# 012_2N3906.net
KiCad netlist of a schematic drawn in Altium Designer
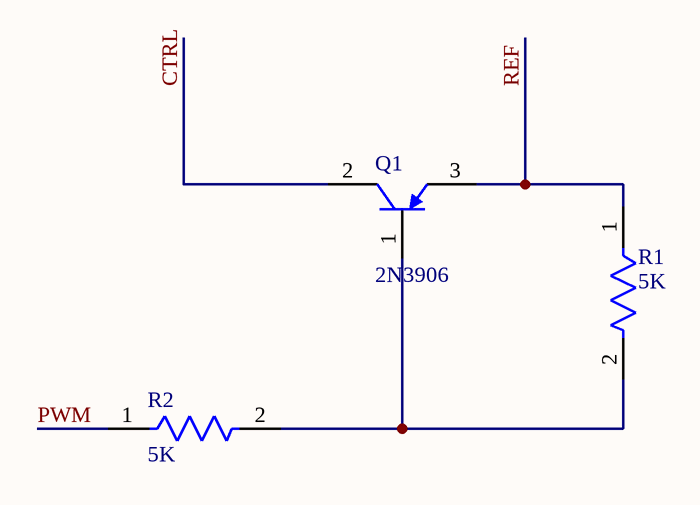
[diagram p0: 012_2N3906.SchDoc]

(export (version "E")
  (design (tool "Eeschema 10.0.6"))
  (components
    (comp (ref "Q1")
      (value "2N3906")
      (footprint "ONSC-SOT-89_PCP-1-3-419AU_V")
      (description "Bipolar Transistor, -50 V, -2 A, Low VCE(sat), PNP Single, 3-Pin SOT-89, Pb-Free, Tape and Reel")
      (fields (field (name "MANUFACTURER") "On Semiconductor") (field (name "PARTNUMBER") "2SB1123S-TD-E"))
      (libsource (lib "Altium Content Vault") (part "ONSC-PNP-B1C2E3-3"))
    )
    (comp (ref "R1")
      (value "5K")
      (footprint "FP-CRCW1206-e3-IPC_C")
      (description "RES Thick Film, 1kΩ, 1%, 0.25W, 100ppm/°C, 1206")
      (fields (field (name "TOLERANCE") "1%"))
      (libsource (lib "Altium Content Vault") (part "1029c3af85768c4190bb7ad29bc67b5"))
    )
    (comp (ref "R2")
      (value "5K")
      (footprint "FP-CRCW1206-e3-IPC_C")
      (description "RES Thick Film, 1kΩ, 1%, 0.25W, 100ppm/°C, 1206")
      (fields (field (name "TOLERANCE") "1%"))
      (libsource (lib "Altium Content Vault") (part "1029c3af85768c4190bb7ad29bc67b5"))
    )
  )
  (nets
    (net (code "1") (name "/CTRL") (class "Default")
      (node (ref "Q1") (pin "2") (pinfunction "C_2") (pintype "passive"))
    )
    (net (code "2") (name "/PWM") (class "Default")
      (node (ref "R2") (pin "1") (pinfunction "1_1") (pintype "passive"))
    )
    (net (code "3") (name "/REF") (class "Default")
      (node (ref "Q1") (pin "3") (pinfunction "E_3") (pintype "passive"))
      (node (ref "R1") (pin "1") (pinfunction "1_1") (pintype "passive"))
    )
    (net (code "4") (name "Net-(Q1-B)") (class "Default")
      (node (ref "Q1") (pin "1") (pinfunction "B_1") (pintype "passive"))
      (node (ref "R1") (pin "2") (pinfunction "2_2") (pintype "passive"))
      (node (ref "R2") (pin "2") (pinfunction "2_2") (pintype "passive"))
    )
  )
)
